# uven2-mk3-cc-driver-single.net
KiCad netlist of a schematic drawn in EasyEDA Pro
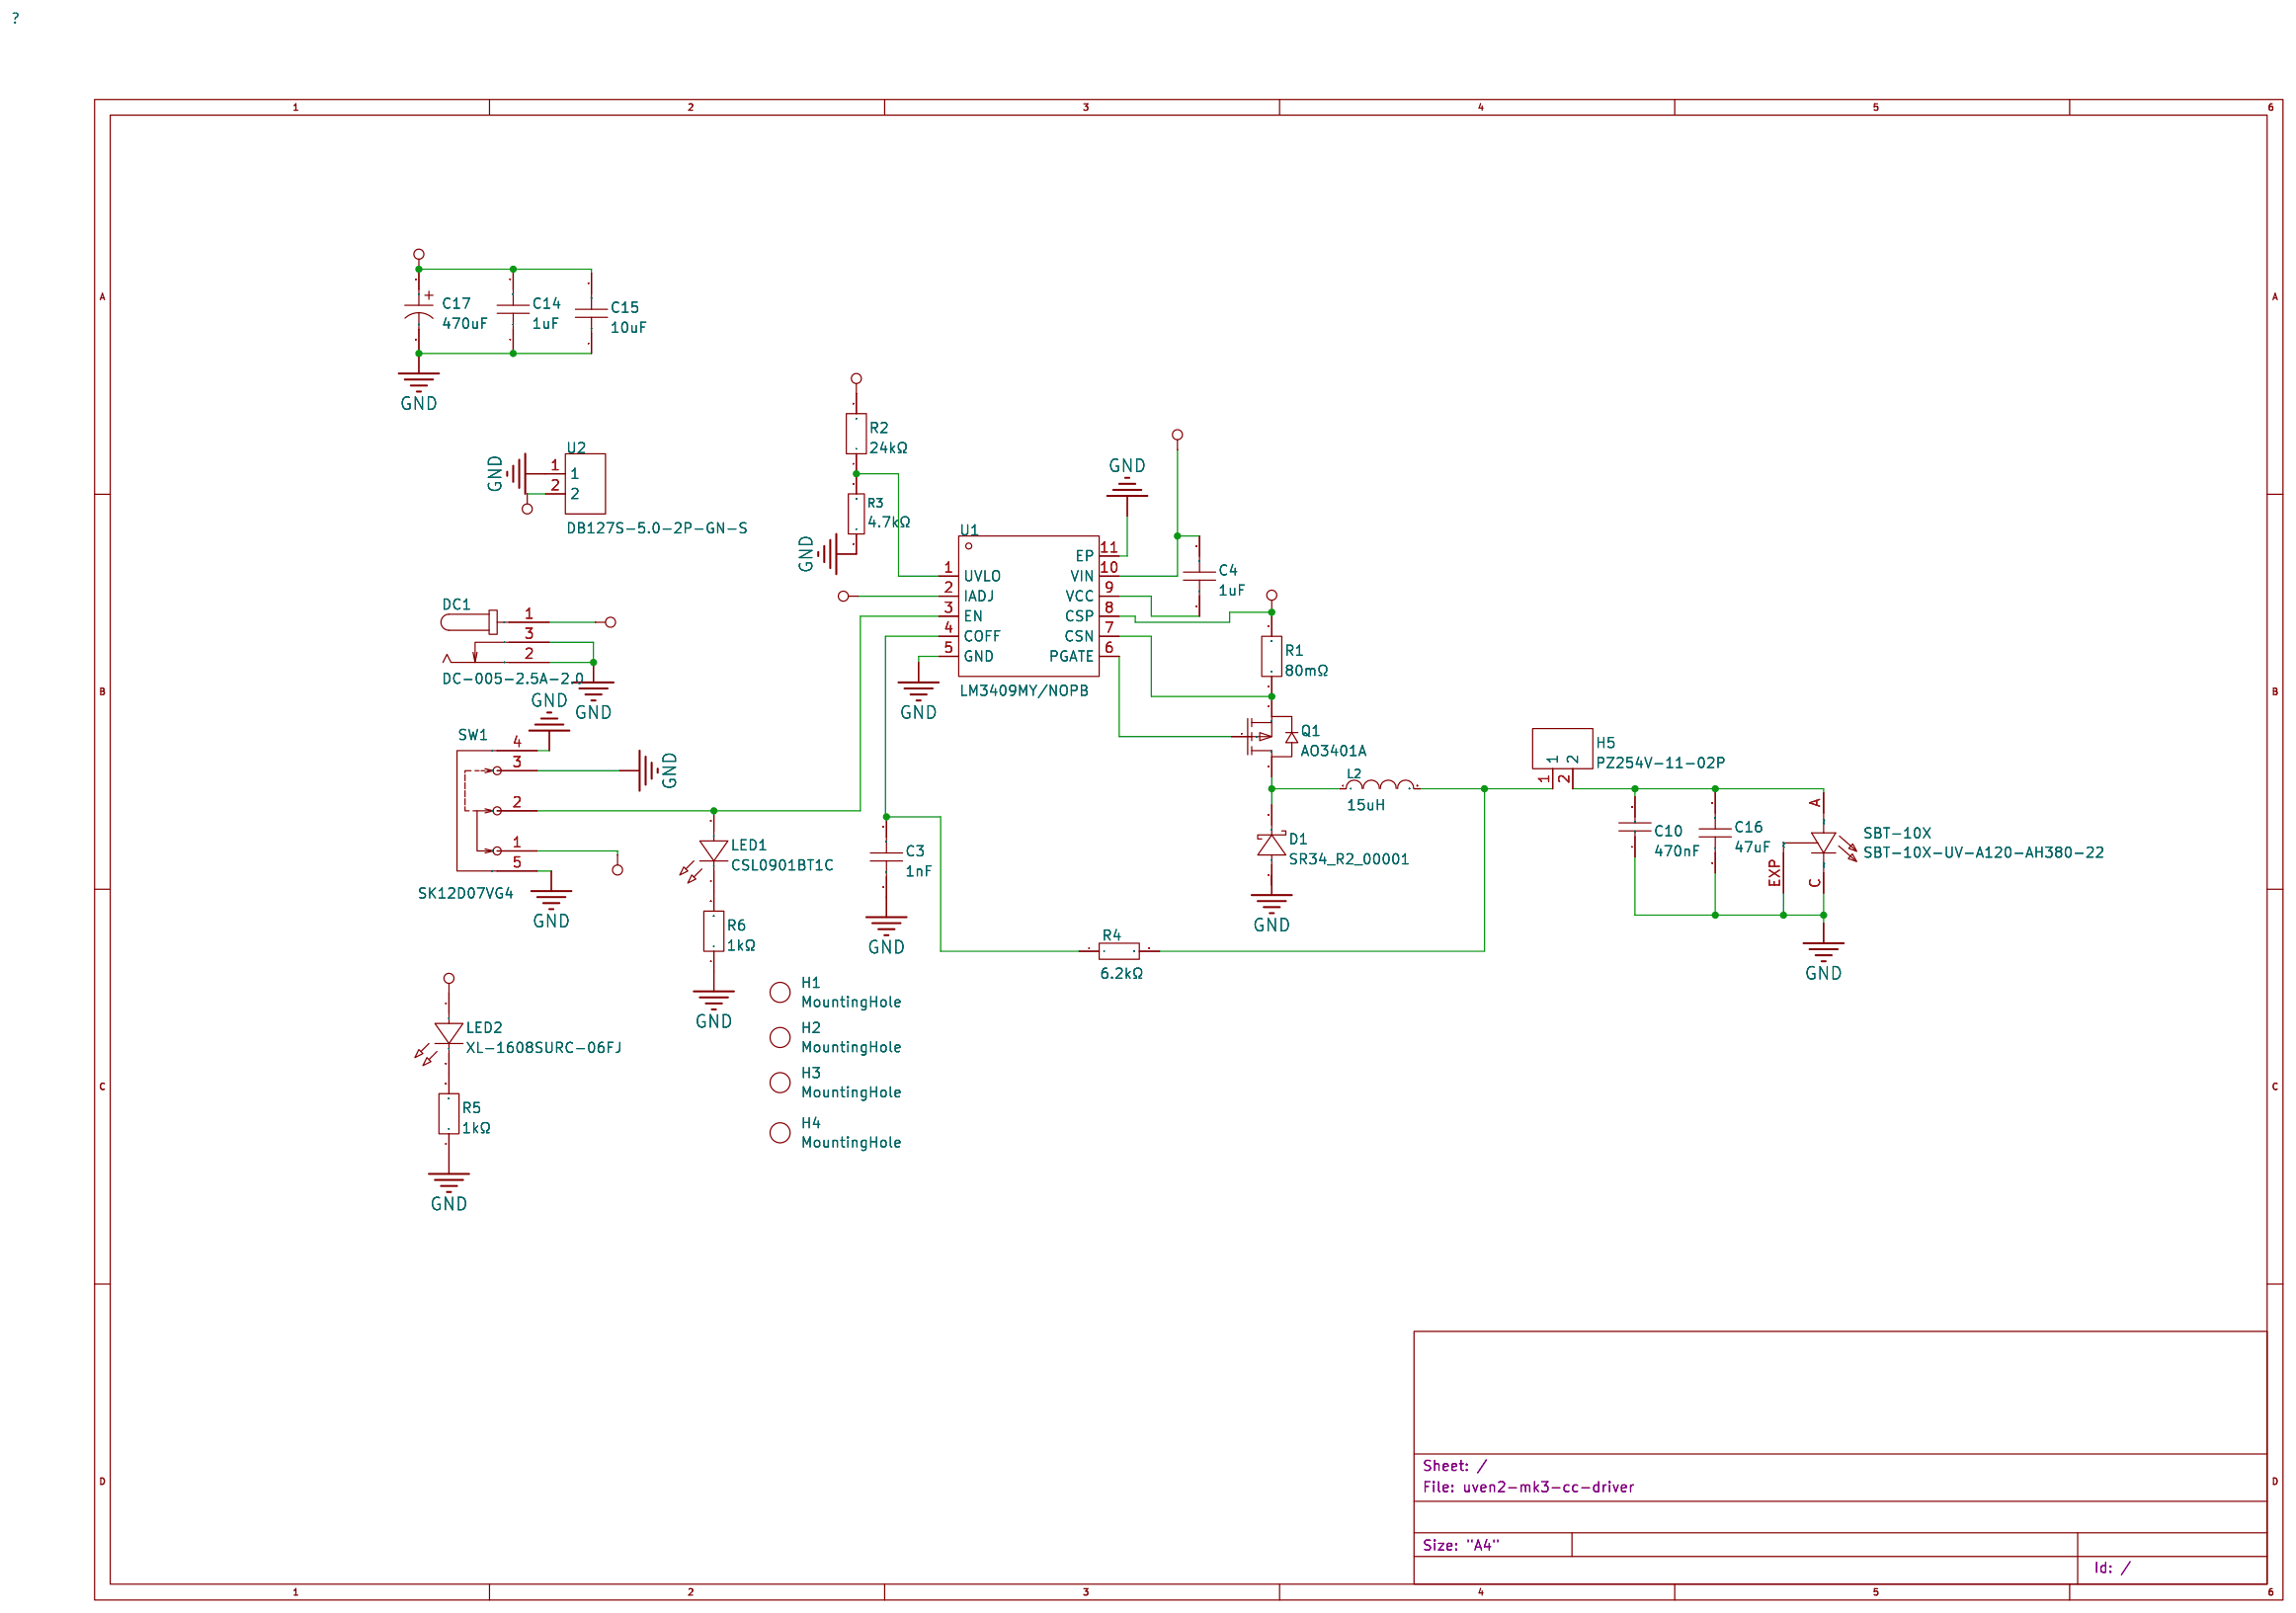
[diagram p0: schematic sheet]

(export (version "E")
  (design (tool "Eeschema 10.0.6"))
  (components
    (comp (ref "C3")
      (value "1nF")
      (footprint "easyedapro:C0402")
      (description "Capacitance:1000pF Tolerance:±20% Tolerance:±20% Voltage Rating:50V Temperature Coefficient:X7R")
      (fields
        (field (name "Manufacturer Part") "TCC0402X7R102M500AT")
        (field (name "Manufacturer") "CCTC(三环)")
      )
      (libsource (lib "easyedapro") (part "TCC0402X7R102M500AT"))
    )
    (comp (ref "C4")
      (value "1uF")
      (footprint "easyedapro:C0603")
      (fields
        (field (name "Manufacturer Part") "CL10A105KB8NNNC")
        (field (name "Manufacturer") "SAMSUNG(三星)")
      )
      (libsource (lib "easyedapro") (part "CL10A105KB8NNNC"))
    )
    (comp (ref "C10")
      (value "470nF")
      (footprint "easyedapro:C0603")
      (fields
        (field (name "Manufacturer Part") "CL10B474KA8NNNC")
        (field (name "Manufacturer") "SAMSUNG(三星)")
      )
      (libsource (lib "easyedapro") (part "CL10B474KA8NNNC"))
    )
    (comp (ref "C14")
      (value "1uF")
      (footprint "easyedapro:C0603")
      (fields
        (field (name "Manufacturer Part") "CL10A105KB8NNNC")
        (field (name "Manufacturer") "SAMSUNG(三星)")
      )
      (libsource (lib "easyedapro") (part "CL10A105KB8NNNC"))
    )
    (comp (ref "C15")
      (value "10uF")
      (footprint "easyedapro:C0805")
      (fields
        (field (name "Manufacturer Part") "GRM21BR61H106KE43L")
        (field (name "Manufacturer") "muRata(村田)")
      )
      (libsource (lib "easyedapro") (part "GRM21BR61H106KE43L"))
    )
    (comp (ref "C16")
      (value "47uF")
      (footprint "easyedapro:C0805")
      (description "Capacitance:47uF Tolerance:±20% Tolerance:±20% Voltage Rating:10V Temperature Coefficient:X5R")
      (fields
        (field (name "Manufacturer Part") "CGA0805X5R476M100MT")
        (field (name "Manufacturer") "HRE(芯声)")
      )
      (libsource (lib "easyedapro") (part "CGA0805X5R476M100MT"))
    )
    (comp (ref "C17")
      (value "470uF")
      (footprint "easyedapro:CAP-SMD_BD8.0-L8.3-W8.3-LS9.1-FD")
      (fields
        (field (name "Manufacturer Part") "GVT1E477M0810CNVC")
        (field (name "Manufacturer") "HRK(鸿瑞凯电子)")
      )
      (libsource (lib "easyedapro") (part "GVT1E477M0810CNVC"))
    )
    (comp (ref "D1")
      (value "SR34_R2_00001")
      (footprint "easyedapro:SMB_L4.3-W3.6-LS5.4-R-RD")
      (fields (field (name "Manufacturer") "PANJIT(强茂)"))
      (libsource (lib "easyedapro") (part "SR34_R2_00001"))
    )
    (comp (ref "DC1")
      (value "DC-005-2.5A-2.0")
      (footprint "easyedapro:CONN-TH_DC-005-2.5A-2.0")
      (fields (field (name "Manufacturer") "XKB Connection(中国星坤)"))
      (libsource (lib "easyedapro") (part "DC-005-2.5A-2.0"))
    )
    (comp (ref "H1")
      (value "MountingHole")
      (footprint "easyedapro:MountingHole:MountingHole_2.2mm_M2")
      (libsource (lib "easyedapro") (part "Mechanical_MountingHole"))
    )
    (comp (ref "H2")
      (value "MountingHole")
      (footprint "easyedapro:MountingHole:MountingHole_2.2mm_M2")
      (libsource (lib "easyedapro") (part "Mechanical_MountingHole"))
    )
    (comp (ref "H3")
      (value "MountingHole")
      (footprint "easyedapro:MountingHole:MountingHole_2.2mm_M2")
      (libsource (lib "easyedapro") (part "Mechanical_MountingHole"))
    )
    (comp (ref "H4")
      (value "MountingHole")
      (footprint "easyedapro:MountingHole:MountingHole_2.2mm_M2")
      (libsource (lib "easyedapro") (part "Mechanical_MountingHole"))
    )
    (comp (ref "H5")
      (value "PZ254V-11-02P")
      (footprint "easyedapro:HDR-TH_2P-P2.54-V-M")
      (fields (field (name "Manufacturer") "XFCN(兴飞)"))
      (libsource (lib "easyedapro") (part "PZ254V-11-02P"))
    )
    (comp (ref "L2")
      (value "15uH")
      (footprint "easyedapro:IND-SMD_L8.0-W8.0-HPC8040NF-150M")
      (fields
        (field (name "Manufacturer Part") "HPC8040NF-150M")
        (field (name "Manufacturer") "TAI-TECH(台庆)")
      )
      (libsource (lib "easyedapro") (part "HPC8040NF-150M"))
    )
    (comp (ref "LED1")
      (value "CSL0901BT1C")
      (footprint "easyedapro:LED0603-RD_BLUE")
      (fields (field (name "Manufacturer") "ROHM(罗姆)"))
      (libsource (lib "easyedapro") (part "CSL0901BT1C"))
    )
    (comp (ref "LED2")
      (value "XL-1608SURC-06FJ")
      (footprint "easyedapro:LED0603-FD")
      (fields (field (name "Manufacturer") "XINGLIGHT(成兴光)"))
      (libsource (lib "easyedapro") (part "XL-1608SURC-06FJ"))
    )
    (comp (ref "Q1")
      (value "AO3401A")
      (footprint "easyedapro:SOT-23-3_L2.9-W1.3-P1.90-LS2.4-BR")
      (fields (field (name "Manufacturer") "TECH PUBLIC(台舟)"))
      (libsource (lib "easyedapro") (part "AO3401A_C5122001"))
    )
    (comp (ref "R1")
      (value "80mΩ")
      (footprint "easyedapro:RES-SMD_L6.4-W3.2-1")
      (fields (field (name "Manufacturer Part") "RLP25FEGR080") (field (name "Manufacturer") "大毅科技"))
      (libsource (lib "easyedapro") (part "RLP25FEGR080"))
    )
    (comp (ref "R2")
      (value "24kΩ")
      (footprint "easyedapro:R0402")
      (fields (field (name "Manufacturer Part") "FRC0402F2402TS") (field (name "Manufacturer") "FOJAN(富捷)"))
      (libsource (lib "easyedapro") (part "FRC0402F2402TS"))
    )
    (comp (ref "R3")
      (value "4.7kΩ")
      (footprint "easyedapro:R0402")
      (fields
        (field (name "Manufacturer Part") "0402WGJ0472TCE")
        (field (name "Manufacturer") "UNI-ROYAL(厚声)")
      )
      (libsource (lib "easyedapro") (part "0402WGJ0472TCE"))
    )
    (comp (ref "R4")
      (value "6.2kΩ")
      (footprint "easyedapro:R0402")
      (fields (field (name "Manufacturer Part") "RC0402FR-076K2L") (field (name "Manufacturer") "YAGEO(国巨)"))
      (libsource (lib "easyedapro") (part "RC0402FR-076K2L"))
    )
    (comp (ref "R5")
      (value "1kΩ")
      (footprint "easyedapro:R0402")
      (fields (field (name "Manufacturer Part") "AC0402FR-7W1KL") (field (name "Manufacturer") "YAGEO(国巨)"))
      (libsource (lib "easyedapro") (part "AC0402FR-7W1KL"))
    )
    (comp (ref "R6")
      (value "1kΩ")
      (footprint "easyedapro:R0402")
      (fields (field (name "Manufacturer Part") "AC0402FR-7W1KL") (field (name "Manufacturer") "YAGEO(国巨)"))
      (libsource (lib "easyedapro") (part "AC0402FR-7W1KL"))
    )
    (comp (ref "SBT-10X")
      (value "SBT-10X-UV-A120-AH380-22")
      (footprint "easyedapro:custom_lib:LED_SBT-10X-UV-A120-AH380-22")
      (fields (field (name "MANUFACTURER") "Luminus Devices"))
      (libsource (lib "easyedapro") (part "SBT-10X-UV-A120-AH380-22_SBT-10X-UV-A120-AH380-22"))
    )
    (comp (ref "SW1")
      (value "SK12D07VG4")
      (footprint "easyedapro:SW-TH_SK12D07VG4")
      (fields (field (name "Manufacturer") "SHOU HAN(首韩)"))
      (libsource (lib "easyedapro") (part "SK12D07VG4"))
    )
    (comp (ref "U1")
      (value "LM3409MY/NOPB")
      (footprint "easyedapro:HVSSOP-10_L3.0-W3.0-P0.50-LS4.9-BL-EP")
      (fields (field (name "Manufacturer") "TI(德州仪器)"))
      (libsource (lib "easyedapro") (part "LM3409MY/NOPB"))
    )
    (comp (ref "U2")
      (value "DB127S-5.0-2P-GN-S")
      (footprint "easyedapro:CONN-TH_DB127S-5.0-2P-GN-S")
      (fields (field (name "Manufacturer") "DORABO(地博电气)"))
      (libsource (lib "easyedapro") (part "DB127S-5.0-2P-GN-S"))
    )
  )
  (nets
    (net (code "1") (name "GND") (class "Default")
      (node (ref "C10") (pin "1") (pinfunction "1_1") (pintype "input"))
      (node (ref "C14") (pin "1") (pinfunction "1_1") (pintype "unspecified"))
      (node (ref "C15") (pin "1") (pinfunction "1_1") (pintype "unspecified"))
      (node (ref "C16") (pin "1") (pinfunction "1_1") (pintype "unspecified"))
      (node (ref "C17") (pin "2") (pinfunction "2_2") (pintype "input"))
      (node (ref "C3") (pin "1") (pinfunction "1_1") (pintype "unspecified"))
      (node (ref "D1") (pin "1") (pinfunction "A_1") (pintype "unspecified"))
      (node (ref "DC1") (pin "2") (pinfunction "2_2") (pintype "unspecified"))
      (node (ref "DC1") (pin "3") (pinfunction "3_3") (pintype "unspecified"))
      (node (ref "R3") (pin "1") (pinfunction "1_1") (pintype "input"))
      (node (ref "R5") (pin "1") (pinfunction "1_1") (pintype "unspecified"))
      (node (ref "R6") (pin "1") (pinfunction "1_1") (pintype "unspecified"))
      (node (ref "SBT-10X") (pin "C") (pinfunction "~_C") (pintype "unspecified"))
      (node (ref "SBT-10X") (pin "EXP") (pinfunction "~_EXP") (pintype "unspecified"))
      (node (ref "SW1") (pin "3") (pinfunction "3_3") (pintype "unspecified"))
      (node (ref "SW1") (pin "4") (pinfunction "4_4") (pintype "unspecified"))
      (node (ref "SW1") (pin "5") (pinfunction "5_5") (pintype "unspecified"))
      (node (ref "U1") (pin "11") (pinfunction "EP_11") (pintype "unspecified"))
      (node (ref "U1") (pin "5") (pinfunction "GND_5") (pintype "unspecified"))
      (node (ref "U2") (pin "1") (pinfunction "1_1") (pintype "unspecified"))
    )
    (net (code "2") (name "LED-DRIVER-RESCUE_VCC-LED-DRIVER-RESCUE") (class "Default")
      (node (ref "C14") (pin "2") (pinfunction "2_2") (pintype "unspecified"))
      (node (ref "C15") (pin "2") (pinfunction "2_2") (pintype "unspecified"))
      (node (ref "C17") (pin "1") (pinfunction "1_1") (pintype "input"))
      (node (ref "C4") (pin "2") (pinfunction "2_2") (pintype "unspecified"))
      (node (ref "DC1") (pin "1") (pinfunction "1_1") (pintype "unspecified"))
      (node (ref "LED2") (pin "1") (pinfunction "A_1") (pintype "unspecified"))
      (node (ref "R1") (pin "2") (pinfunction "2_2") (pintype "unspecified"))
      (node (ref "R2") (pin "2") (pinfunction "2_2") (pintype "unspecified"))
      (node (ref "SW1") (pin "1") (pinfunction "1_1") (pintype "unspecified"))
      (node (ref "U1") (pin "10") (pinfunction "VIN_10") (pintype "unspecified"))
      (node (ref "U1") (pin "2") (pinfunction "IADJ_2") (pintype "unspecified"))
      (node (ref "U1") (pin "8") (pinfunction "CSP_8") (pintype "unspecified"))
      (node (ref "U2") (pin "2") (pinfunction "2_2") (pintype "unspecified"))
    )
    (net (code "3") (name "Net-(C10-Pad2)") (class "Default")
      (node (ref "C10") (pin "2") (pinfunction "2_2") (pintype "input"))
      (node (ref "C16") (pin "2") (pinfunction "2_2") (pintype "unspecified"))
      (node (ref "H5") (pin "2") (pinfunction "2_2") (pintype "unspecified"))
      (node (ref "SBT-10X") (pin "A") (pinfunction "~_A") (pintype "unspecified"))
    )
    (net (code "4") (name "Net-(D1-K)") (class "Default")
      (node (ref "D1") (pin "2") (pinfunction "K_2") (pintype "unspecified"))
      (node (ref "L2") (pin "1") (pinfunction "1_1") (pintype "input"))
      (node (ref "Q1") (pin "3") (pinfunction "D_3") (pintype "unspecified"))
    )
    (net (code "5") (name "Net-(H5-Pad1)") (class "Default")
      (node (ref "H5") (pin "1") (pinfunction "1_1") (pintype "unspecified"))
      (node (ref "L2") (pin "2") (pinfunction "2_2") (pintype "input"))
      (node (ref "R4") (pin "2") (pinfunction "2_2") (pintype "input"))
    )
    (net (code "6") (name "Net-(LED1-A)") (class "Default")
      (node (ref "LED1") (pin "2") (pinfunction "A_2") (pintype "unspecified"))
      (node (ref "SW1") (pin "2") (pinfunction "2_2") (pintype "unspecified"))
      (node (ref "U1") (pin "3") (pinfunction "EN_3") (pintype "unspecified"))
    )
    (net (code "7") (name "Net-(LED1-K)") (class "Default")
      (node (ref "LED1") (pin "1") (pinfunction "K_1") (pintype "unspecified"))
      (node (ref "R6") (pin "2") (pinfunction "2_2") (pintype "unspecified"))
    )
    (net (code "8") (name "Net-(LED2-K)") (class "Default")
      (node (ref "LED2") (pin "2") (pinfunction "K_2") (pintype "unspecified"))
      (node (ref "R5") (pin "2") (pinfunction "2_2") (pintype "unspecified"))
    )
    (net (code "9") (name "Net-(Q1-G)") (class "Default")
      (node (ref "Q1") (pin "1") (pinfunction "G_1") (pintype "unspecified"))
      (node (ref "U1") (pin "6") (pinfunction "PGATE_6") (pintype "unspecified"))
    )
    (net (code "10") (name "Net-(Q1-S)") (class "Default")
      (node (ref "Q1") (pin "2") (pinfunction "S_2") (pintype "unspecified"))
      (node (ref "R1") (pin "1") (pinfunction "1_1") (pintype "unspecified"))
      (node (ref "U1") (pin "7") (pinfunction "CSN_7") (pintype "unspecified"))
    )
    (net (code "11") (name "Net-(U1-COFF)") (class "Default")
      (node (ref "C3") (pin "2") (pinfunction "2_2") (pintype "unspecified"))
      (node (ref "R4") (pin "1") (pinfunction "1_1") (pintype "input"))
      (node (ref "U1") (pin "4") (pinfunction "COFF_4") (pintype "unspecified"))
    )
    (net (code "12") (name "Net-(U1-UVLO)") (class "Default")
      (node (ref "R2") (pin "1") (pinfunction "1_1") (pintype "unspecified"))
      (node (ref "R3") (pin "2") (pinfunction "2_2") (pintype "input"))
      (node (ref "U1") (pin "1") (pinfunction "UVLO_1") (pintype "unspecified"))
    )
    (net (code "13") (name "Net-(U1-VCC)") (class "Default")
      (node (ref "C4") (pin "1") (pinfunction "1_1") (pintype "unspecified"))
      (node (ref "U1") (pin "9") (pinfunction "VCC_9") (pintype "unspecified"))
    )
  )
)
